# RockBlock_Breakout.net
KiCad netlist of a schematic drawn in EAGLE
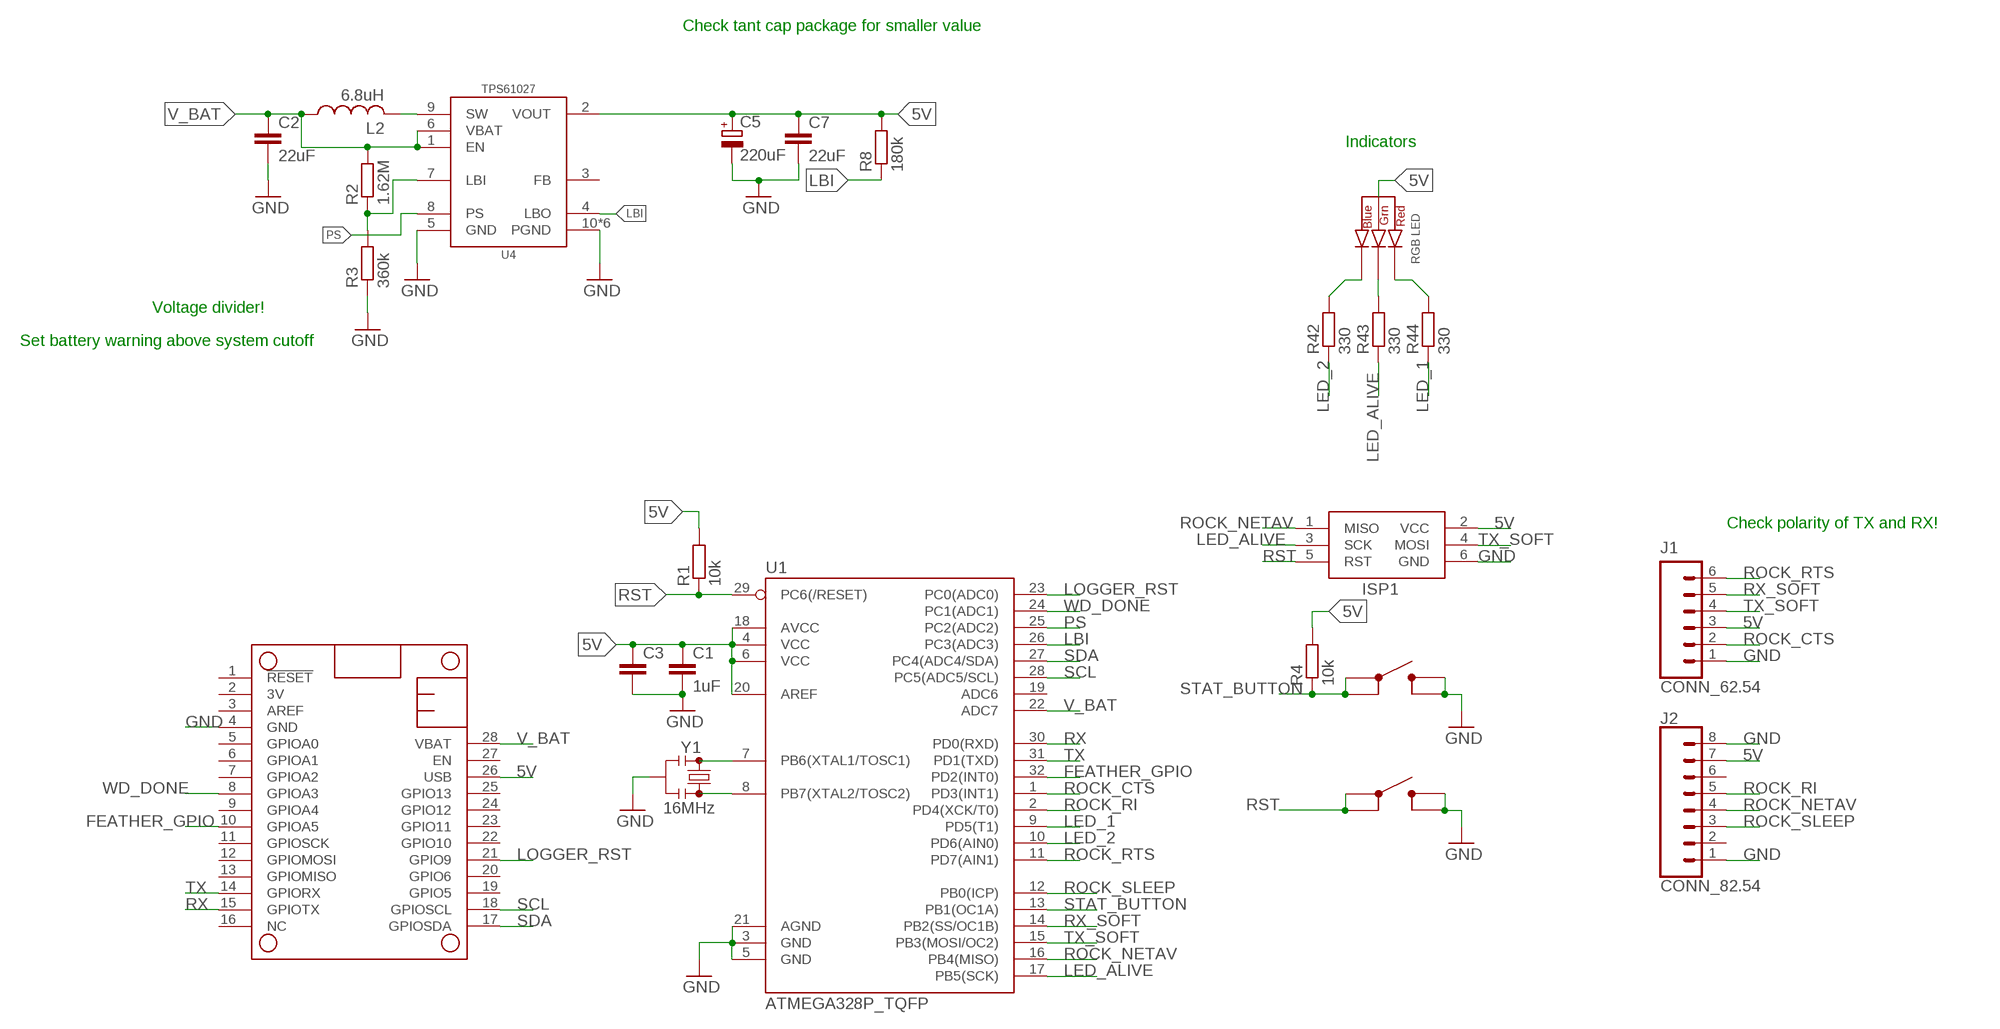
[diagram p0: schematic, sheet 1]

(export (version "E")
  (design (tool "Eeschema 10.0.6"))
  (components
    (comp (ref "C1")
      (value "1uF")
      (footprint "eagle-import:C0603")
      (libsource (lib "eagle-import") (part "C-EUC0603"))
    )
    (comp (ref "C2")
      (value "22uF")
      (footprint "eagle-import:C0805")
      (fields (field (name "MF") "Murata") (field (name "MPN") "GRM219R61C226ME15L"))
      (libsource (lib "eagle-import") (part "C-EUC080522UF"))
    )
    (comp (ref "C3")
      (value "C-EUC0402")
      (footprint "eagle-import:C0402")
      (libsource (lib "eagle-import") (part "C-EUC0402"))
    )
    (comp (ref "C5")
      (value "220uF")
      (footprint "eagle-import:C2917")
      (fields (field (name "MF") "AVX") (field (name "MPN") "TPSY227K010R0100"))
      (libsource (lib "eagle-import") (part "CTANT_EU2917"))
    )
    (comp (ref "C7")
      (value "22uF")
      (footprint "eagle-import:C0805")
      (fields (field (name "MF") "Murata") (field (name "MPN") "GRM219R61C226ME15L"))
      (libsource (lib "eagle-import") (part "C-EUC080522UF"))
    )
    (comp (ref "D5")
      (value "CLVBA-FKA")
      (footprint "eagle-import:CLVBA-FKA")
      (fields (field (name "MF") "Cree") (field (name "MPN") "CLVBA-FKA-CAEDH8BBB7A363"))
      (libsource (lib "eagle-import") (part "CLVBA-FKA"))
    )
    (comp (ref "ISP1")
      (value "AVRISP-6")
      (footprint "eagle-import:AVRISP")
      (libsource (lib "eagle-import") (part "AVRISP-6"))
    )
    (comp (ref "J1")
      (value "CONN_62.54")
      (footprint "eagle-import:1X06")
      (libsource (lib "eagle-import") (part "CONN_62.54"))
    )
    (comp (ref "J2")
      (value "CONN_82.54")
      (footprint "eagle-import:1X08")
      (libsource (lib "eagle-import") (part "CONN_82.54"))
    )
    (comp (ref "L2")
      (value "6.8uH")
      (footprint "eagle-import:WE-TPC(4.8X4.8)")
      (fields (field (name "MF") "Wurth") (field (name "MPN") "744042006"))
      (libsource (lib "eagle-import") (part "INDUCTORTPC_4.8X4.8"))
    )
    (comp (ref "MS1")
      (value "FEATHERWINGLAYOUT")
      (footprint "eagle-import:FEATHERWING_MIN")
      (libsource (lib "eagle-import") (part "FEATHERWINGLAYOUT"))
    )
    (comp (ref "R1")
      (value "10k")
      (footprint "eagle-import:R0402")
      (fields (field (name "MF") "Yageo"))
      (libsource (lib "eagle-import") (part "R-EU_R0402"))
    )
    (comp (ref "R2")
      (value "1.62M")
      (footprint "eagle-import:R0603")
      (fields (field (name "MF") "Stackpole") (field (name "MPN") "RMCF0603FT1M62"))
      (libsource (lib "eagle-import") (part "R-EU_R06031.62M"))
    )
    (comp (ref "R3")
      (value "360k")
      (footprint "eagle-import:R0603")
      (fields (field (name "MF") "Yageo") (field (name "MPN") "RC0603FR-07360KL"))
      (libsource (lib "eagle-import") (part "R-EU_R0603360K"))
    )
    (comp (ref "R4")
      (value "10k")
      (footprint "eagle-import:R0402")
      (fields (field (name "MF") "Yageo"))
      (libsource (lib "eagle-import") (part "R-EU_R0402"))
    )
    (comp (ref "R8")
      (value "180k")
      (footprint "eagle-import:R0603")
      (fields (field (name "MF") "Panasonic") (field (name "MPN") "ERJ-3EKF1803V"))
      (libsource (lib "eagle-import") (part "R-EU_R0603180K"))
    )
    (comp (ref "R42")
      (value "330")
      (footprint "eagle-import:R0402")
      (fields
        (field (name "MF") "Yageo")
        (field (name "MPN") "RC0402FR-07330RL")
        (field (name "MPN_1") "RC0603FR-07330RL")
      )
      (libsource (lib "eagle-import") (part "R-EU_R0402330"))
    )
    (comp (ref "R43")
      (value "330")
      (footprint "eagle-import:R0402")
      (fields
        (field (name "MF") "Yageo")
        (field (name "MPN") "RC0402FR-07330RL")
        (field (name "MPN_1") "RC0603FR-07330RL")
      )
      (libsource (lib "eagle-import") (part "R-EU_R0402330"))
    )
    (comp (ref "R44")
      (value "330")
      (footprint "eagle-import:R0402")
      (fields
        (field (name "MF") "Yageo")
        (field (name "MPN") "RC0402FR-07330RL")
        (field (name "MPN_1") "RC0603FR-07330RL")
      )
      (libsource (lib "eagle-import") (part "R-EU_R0402330"))
    )
    (comp (ref "S1")
      (value "BUTTON4.2X3.2")
      (footprint "eagle-import:SWITCH_4.2X3.2")
      (fields (field (name "MF") "C&K") (field (name "MPN") "PTS810 SJG 250 SMTR LFS"))
      (libsource (lib "eagle-import") (part "BUTTON4.2X3.2"))
    )
    (comp (ref "S2")
      (value "BUTTON4.2X3.2")
      (footprint "eagle-import:SWITCH_4.2X3.2")
      (fields (field (name "MF") "C&K") (field (name "MPN") "PTS810 SJG 250 SMTR LFS"))
      (libsource (lib "eagle-import") (part "BUTTON4.2X3.2"))
    )
    (comp (ref "U1")
      (value "ATMEGA328P_TQFP")
      (footprint "eagle-import:TQFP32-08")
      (fields (field (name "MF") "Atmel") (field (name "MPN") "ATMEGA328PB-AUR"))
      (libsource (lib "eagle-import") (part "ATMEGA328P_TQFP"))
    )
    (comp (ref "U4")
      (value "TPS61027DRC")
      (footprint "eagle-import:DRC0010J")
      (fields (field (name "DISP") "TPS61027") (field (name "MF") "TI") (field (name "MPN") "TPS61027DRCR"))
      (libsource (lib "eagle-import") (part "TPS6102DRC7"))
    )
    (comp (ref "Y1")
      (value "16MHz")
      (footprint "eagle-import:RESONATOR-SMD-3.2X1.3")
      (fields (field (name "MF") "Murata") (field (name "MPN") "CSTNE16M0V530000R0"))
      (libsource (lib "eagle-import") (part "RESONATORSMD_3.2X1.316MHZ"))
    )
  )
  (nets
    (net (code "1") (name "/3V") (class "Default")
      (node (ref "MS1") (pin "2") (pinfunction "3V_2") (pintype "power_in"))
    )
    (net (code "2") (name "/FEATHER_GPIO") (class "Default")
      (node (ref "MS1") (pin "10") (pinfunction "GPIOA5_10") (pintype "bidirectional"))
      (node (ref "U1") (pin "32") (pinfunction "PD2(INT0)_32") (pintype "bidirectional"))
    )
    (net (code "3") (name "/LED_1") (class "Default")
      (node (ref "R44") (pin "1") (pinfunction "1_1") (pintype "passive"))
      (node (ref "U1") (pin "9") (pinfunction "PD5(T1)_9") (pintype "bidirectional"))
    )
    (net (code "4") (name "/LED_2") (class "Default")
      (node (ref "R42") (pin "1") (pinfunction "1_1") (pintype "passive"))
      (node (ref "U1") (pin "10") (pinfunction "PD6(AIN0)_10") (pintype "bidirectional"))
    )
    (net (code "5") (name "/LED_ALIVE") (class "Default")
      (node (ref "ISP1") (pin "3") (pinfunction "SCK_3") (pintype "output"))
      (node (ref "R43") (pin "1") (pinfunction "1_1") (pintype "passive"))
      (node (ref "U1") (pin "17") (pinfunction "PB5(SCK)_17") (pintype "bidirectional"))
    )
    (net (code "6") (name "/LOGGER_RST") (class "Default")
      (node (ref "MS1") (pin "21") (pinfunction "GPIO9_21") (pintype "bidirectional"))
      (node (ref "U1") (pin "23") (pinfunction "PC0(ADC0)_23") (pintype "bidirectional"))
    )
    (net (code "7") (name "/ROCK_CTS") (class "Default")
      (node (ref "J1") (pin "2") (pinfunction "2_2") (pintype "passive"))
      (node (ref "U1") (pin "1") (pinfunction "PD3(INT1)_1") (pintype "bidirectional"))
    )
    (net (code "8") (name "/ROCK_NETAV") (class "Default")
      (node (ref "ISP1") (pin "1") (pinfunction "MISO_1") (pintype "input"))
      (node (ref "J2") (pin "4") (pinfunction "4_4") (pintype "passive"))
      (node (ref "U1") (pin "16") (pinfunction "PB4(MISO)_16") (pintype "bidirectional"))
    )
    (net (code "9") (name "/ROCK_RI") (class "Default")
      (node (ref "J2") (pin "5") (pinfunction "5_5") (pintype "passive"))
      (node (ref "U1") (pin "2") (pinfunction "PD4(XCK/T0)_2") (pintype "bidirectional"))
    )
    (net (code "10") (name "/ROCK_RTS") (class "Default")
      (node (ref "J1") (pin "6") (pinfunction "6_6") (pintype "passive"))
      (node (ref "U1") (pin "11") (pinfunction "PD7(AIN1)_11") (pintype "bidirectional"))
    )
    (net (code "11") (name "/ROCK_SLEEP") (class "Default")
      (node (ref "J2") (pin "3") (pinfunction "3_3") (pintype "passive"))
      (node (ref "U1") (pin "12") (pinfunction "PB0(ICP)_12") (pintype "bidirectional"))
    )
    (net (code "12") (name "/RX") (class "Default")
      (node (ref "MS1") (pin "15") (pinfunction "GPIOTX_15") (pintype "bidirectional"))
      (node (ref "U1") (pin "30") (pinfunction "PD0(RXD)_30") (pintype "bidirectional"))
    )
    (net (code "13") (name "/RX_SOFT") (class "Default")
      (node (ref "J1") (pin "5") (pinfunction "5_5") (pintype "passive"))
      (node (ref "U1") (pin "14") (pinfunction "PB2(SS/OC1B)_14") (pintype "bidirectional"))
    )
    (net (code "14") (name "/SCL") (class "Default")
      (node (ref "MS1") (pin "18") (pinfunction "GPIOSCL_18") (pintype "bidirectional"))
      (node (ref "U1") (pin "28") (pinfunction "PC5(ADC5/SCL)_28") (pintype "bidirectional"))
    )
    (net (code "15") (name "/SDA") (class "Default")
      (node (ref "MS1") (pin "17") (pinfunction "GPIOSDA_17") (pintype "bidirectional"))
      (node (ref "U1") (pin "27") (pinfunction "PC4(ADC4/SDA)_27") (pintype "bidirectional"))
    )
    (net (code "16") (name "/STAT_BUTTON") (class "Default")
      (node (ref "R4") (pin "1") (pinfunction "1_1") (pintype "passive"))
      (node (ref "S1") (pin "1") (pinfunction "1_1") (pintype "bidirectional"))
      (node (ref "S1") (pin "2") (pinfunction "2_2") (pintype "bidirectional"))
      (node (ref "U1") (pin "13") (pinfunction "PB1(OC1A)_13") (pintype "bidirectional"))
    )
    (net (code "17") (name "/TX") (class "Default")
      (node (ref "MS1") (pin "14") (pinfunction "GPIORX_14") (pintype "bidirectional"))
      (node (ref "U1") (pin "31") (pinfunction "PD1(TXD)_31") (pintype "bidirectional"))
    )
    (net (code "18") (name "/TX_SOFT") (class "Default")
      (node (ref "ISP1") (pin "4") (pinfunction "MOSI_4") (pintype "output"))
      (node (ref "J1") (pin "4") (pinfunction "4_4") (pintype "passive"))
      (node (ref "U1") (pin "15") (pinfunction "PB3(MOSI/OC2)_15") (pintype "bidirectional"))
    )
    (net (code "19") (name "/WD_DONE") (class "Default")
      (node (ref "MS1") (pin "8") (pinfunction "GPIOA3_8") (pintype "bidirectional"))
      (node (ref "U1") (pin "24") (pinfunction "PC1(ADC1)_24") (pintype "bidirectional"))
    )
    (net (code "20") (name "5V") (class "Default")
      (node (ref "C1") (pin "1") (pinfunction "1_1") (pintype "passive"))
      (node (ref "C3") (pin "1") (pinfunction "1_1") (pintype "passive"))
      (node (ref "C5") (pin "+") (pinfunction "+_+") (pintype "passive"))
      (node (ref "C7") (pin "1") (pinfunction "1_1") (pintype "passive"))
      (node (ref "D5") (pin "2") (pinfunction "ANODE_2") (pintype "bidirectional"))
      (node (ref "ISP1") (pin "2") (pinfunction "VCC_2") (pintype "power_in"))
      (node (ref "J1") (pin "3") (pinfunction "3_3") (pintype "passive"))
      (node (ref "J2") (pin "7") (pinfunction "7_7") (pintype "passive"))
      (node (ref "MS1") (pin "26") (pinfunction "USB_26") (pintype "power_in"))
      (node (ref "R1") (pin "2") (pinfunction "2_2") (pintype "passive"))
      (node (ref "R4") (pin "2") (pinfunction "2_2") (pintype "passive"))
      (node (ref "R8") (pin "2") (pinfunction "2_2") (pintype "passive"))
      (node (ref "U1") (pin "18") (pinfunction "AVCC_18") (pintype "bidirectional"))
      (node (ref "U1") (pin "20") (pinfunction "AREF_20") (pintype "bidirectional"))
      (node (ref "U1") (pin "4") (pinfunction "VCC_4") (pintype "bidirectional"))
      (node (ref "U1") (pin "6") (pinfunction "VCC_6") (pintype "bidirectional"))
      (node (ref "U4") (pin "2") (pinfunction "VOUT_2") (pintype "power_in"))
    )
    (net (code "21") (name "GND") (class "Default")
      (node (ref "C1") (pin "2") (pinfunction "2_2") (pintype "passive"))
      (node (ref "C2") (pin "2") (pinfunction "2_2") (pintype "passive"))
      (node (ref "C3") (pin "2") (pinfunction "2_2") (pintype "passive"))
      (node (ref "C5") (pin "-") (pinfunction "-_-") (pintype "passive"))
      (node (ref "C7") (pin "2") (pinfunction "2_2") (pintype "passive"))
      (node (ref "ISP1") (pin "6") (pinfunction "GND_6") (pintype "power_in"))
      (node (ref "J1") (pin "1") (pinfunction "1_1") (pintype "passive"))
      (node (ref "J2") (pin "1") (pinfunction "1_1") (pintype "passive"))
      (node (ref "J2") (pin "8") (pinfunction "8_8") (pintype "passive"))
      (node (ref "MS1") (pin "4") (pinfunction "GND_4") (pintype "power_in"))
      (node (ref "R3") (pin "1") (pinfunction "1_1") (pintype "passive"))
      (node (ref "S1") (pin "3") (pinfunction "4_3") (pintype "bidirectional"))
      (node (ref "S1") (pin "4") (pinfunction "3_4") (pintype "bidirectional"))
      (node (ref "S2") (pin "3") (pinfunction "4_3") (pintype "bidirectional"))
      (node (ref "S2") (pin "4") (pinfunction "3_4") (pintype "bidirectional"))
      (node (ref "U1") (pin "21") (pinfunction "AGND_21") (pintype "bidirectional"))
      (node (ref "U1") (pin "3") (pinfunction "GND_3") (pintype "bidirectional"))
      (node (ref "U1") (pin "5") (pinfunction "GND_5") (pintype "bidirectional"))
      (node (ref "U4") (pin "10") (pinfunction "PGND_10") (pintype "power_in"))
      (node (ref "U4") (pin "5") (pinfunction "GND_5") (pintype "power_in"))
      (node (ref "U4") (pin "EP@1") (pinfunction "PGND_EP@1") (pintype "power_in"))
      (node (ref "U4") (pin "EP@2") (pinfunction "PGND_EP@2") (pintype "power_in"))
      (node (ref "U4") (pin "EP@3") (pinfunction "PGND_EP@3") (pintype "power_in"))
      (node (ref "U4") (pin "EP@4") (pinfunction "PGND_EP@4") (pintype "power_in"))
      (node (ref "U4") (pin "EP@5") (pinfunction "PGND_EP@5") (pintype "power_in"))
      (node (ref "Y1") (pin "2") (pinfunction "2_2") (pintype "passive"))
    )
    (net (code "22") (name "LBI") (class "Default")
      (node (ref "R8") (pin "1") (pinfunction "1_1") (pintype "passive"))
      (node (ref "U1") (pin "26") (pinfunction "PC3(ADC3)_26") (pintype "bidirectional"))
      (node (ref "U4") (pin "4") (pinfunction "LBO_4") (pintype "output"))
    )
    (net (code "23") (name "Net-(D5-BLUE_CATH)") (class "Default")
      (node (ref "D5") (pin "3") (pinfunction "BLUE_CATH_3") (pintype "bidirectional"))
      (node (ref "R42") (pin "2") (pinfunction "2_2") (pintype "passive"))
    )
    (net (code "24") (name "Net-(D5-GREEN_CATH)") (class "Default")
      (node (ref "D5") (pin "4") (pinfunction "GREEN_CATH_4") (pintype "bidirectional"))
      (node (ref "R43") (pin "2") (pinfunction "2_2") (pintype "passive"))
    )
    (net (code "25") (name "Net-(D5-RED_CATH)") (class "Default")
      (node (ref "D5") (pin "1") (pinfunction "RED_CATH_1") (pintype "bidirectional"))
      (node (ref "R44") (pin "2") (pinfunction "2_2") (pintype "passive"))
    )
    (net (code "26") (name "Net-(U1-PB6(XTAL1{slash}TOSC1))") (class "Default")
      (node (ref "U1") (pin "7") (pinfunction "PB6(XTAL1/TOSC1)_7") (pintype "bidirectional"))
      (node (ref "Y1") (pin "1") (pinfunction "1_1") (pintype "passive"))
    )
    (net (code "27") (name "Net-(U1-PB7(XTAL2{slash}TOSC2))") (class "Default")
      (node (ref "U1") (pin "8") (pinfunction "PB7(XTAL2/TOSC2)_8") (pintype "bidirectional"))
      (node (ref "Y1") (pin "3") (pinfunction "3_3") (pintype "passive"))
    )
    (net (code "28") (name "Net-(U4-LBI)") (class "Default")
      (node (ref "R2") (pin "1") (pinfunction "1_1") (pintype "passive"))
      (node (ref "R3") (pin "2") (pinfunction "2_2") (pintype "passive"))
      (node (ref "U4") (pin "7") (pinfunction "LBI_7") (pintype "input"))
    )
    (net (code "29") (name "Net-(U4-SW)") (class "Default")
      (node (ref "L2") (pin "2") (pinfunction "2_2") (pintype "passive"))
      (node (ref "U4") (pin "9") (pinfunction "SW_9") (pintype "power_in"))
    )
    (net (code "30") (name "PS") (class "Default")
      (node (ref "U1") (pin "25") (pinfunction "PC2(ADC2)_25") (pintype "bidirectional"))
      (node (ref "U4") (pin "8") (pinfunction "PS_8") (pintype "input"))
    )
    (net (code "31") (name "RST") (class "Default")
      (node (ref "ISP1") (pin "5") (pinfunction "RST_5") (pintype "output"))
      (node (ref "R1") (pin "1") (pinfunction "1_1") (pintype "passive"))
      (node (ref "S2") (pin "1") (pinfunction "1_1") (pintype "bidirectional"))
      (node (ref "S2") (pin "2") (pinfunction "2_2") (pintype "bidirectional"))
      (node (ref "U1") (pin "29") (pinfunction "PC6(/RESET)_29") (pintype "bidirectional"))
    )
    (net (code "32") (name "V_BAT") (class "Default")
      (node (ref "C2") (pin "1") (pinfunction "1_1") (pintype "passive"))
      (node (ref "L2") (pin "1") (pinfunction "1_1") (pintype "passive"))
      (node (ref "MS1") (pin "28") (pinfunction "VBAT_28") (pintype "power_in"))
      (node (ref "R2") (pin "2") (pinfunction "2_2") (pintype "passive"))
      (node (ref "U1") (pin "22") (pinfunction "ADC7_22") (pintype "bidirectional"))
      (node (ref "U4") (pin "1") (pinfunction "EN_1") (pintype "input"))
      (node (ref "U4") (pin "6") (pinfunction "VBAT_6") (pintype "power_in"))
    )
    (net (code "33") (name "unconnected-(J2-Pad2)") (class "Default")
      (node (ref "J2") (pin "2") (pinfunction "2_2") (pintype "passive"))
    )
    (net (code "34") (name "unconnected-(J2-Pad6)") (class "Default")
      (node (ref "J2") (pin "6") (pinfunction "6_6") (pintype "passive"))
    )
    (net (code "35") (name "unconnected-(MS1-AREF-Pad3)") (class "Default")
      (node (ref "MS1") (pin "3") (pinfunction "AREF_3") (pintype "passive"))
    )
    (net (code "36") (name "unconnected-(MS1-EN-Pad27)") (class "Default")
      (node (ref "MS1") (pin "27") (pinfunction "EN_27") (pintype "passive"))
    )
    (net (code "37") (name "unconnected-(MS1-GPIO5-Pad19)") (class "Default")
      (node (ref "MS1") (pin "19") (pinfunction "GPIO5_19") (pintype "bidirectional"))
    )
    (net (code "38") (name "unconnected-(MS1-GPIO6-Pad20)") (class "Default")
      (node (ref "MS1") (pin "20") (pinfunction "GPIO6_20") (pintype "bidirectional"))
    )
    (net (code "39") (name "unconnected-(MS1-GPIO10-Pad22)") (class "Default")
      (node (ref "MS1") (pin "22") (pinfunction "GPIO10_22") (pintype "bidirectional"))
    )
    (net (code "40") (name "unconnected-(MS1-GPIO11-Pad23)") (class "Default")
      (node (ref "MS1") (pin "23") (pinfunction "GPIO11_23") (pintype "bidirectional"))
    )
    (net (code "41") (name "unconnected-(MS1-GPIO12-Pad24)") (class "Default")
      (node (ref "MS1") (pin "24") (pinfunction "GPIO12_24") (pintype "bidirectional"))
    )
    (net (code "42") (name "unconnected-(MS1-GPIO13-Pad25)") (class "Default")
      (node (ref "MS1") (pin "25") (pinfunction "GPIO13_25") (pintype "bidirectional"))
    )
    (net (code "43") (name "unconnected-(MS1-GPIOA0-Pad5)") (class "Default")
      (node (ref "MS1") (pin "5") (pinfunction "GPIOA0_5") (pintype "bidirectional"))
    )
    (net (code "44") (name "unconnected-(MS1-GPIOA1-Pad6)") (class "Default")
      (node (ref "MS1") (pin "6") (pinfunction "GPIOA1_6") (pintype "bidirectional"))
    )
    (net (code "45") (name "unconnected-(MS1-GPIOA2-Pad7)") (class "Default")
      (node (ref "MS1") (pin "7") (pinfunction "GPIOA2_7") (pintype "bidirectional"))
    )
    (net (code "46") (name "unconnected-(MS1-GPIOA4-Pad9)") (class "Default")
      (node (ref "MS1") (pin "9") (pinfunction "GPIOA4_9") (pintype "bidirectional"))
    )
    (net (code "47") (name "unconnected-(MS1-GPIOMISO-Pad13)") (class "Default")
      (node (ref "MS1") (pin "13") (pinfunction "GPIOMISO_13") (pintype "bidirectional"))
    )
    (net (code "48") (name "unconnected-(MS1-GPIOMOSI-Pad12)") (class "Default")
      (node (ref "MS1") (pin "12") (pinfunction "GPIOMOSI_12") (pintype "bidirectional"))
    )
    (net (code "49") (name "unconnected-(MS1-GPIOSCK-Pad11)") (class "Default")
      (node (ref "MS1") (pin "11") (pinfunction "GPIOSCK_11") (pintype "bidirectional"))
    )
    (net (code "50") (name "unconnected-(MS1-NC-Pad16)") (class "Default")
      (node (ref "MS1") (pin "16") (pinfunction "NC_16") (pintype "passive"))
    )
    (net (code "51") (name "unconnected-(MS1-~{RESET}-Pad1)") (class "Default")
      (node (ref "MS1") (pin "1") (pinfunction "~{RESET}_1") (pintype "input"))
    )
    (net (code "52") (name "unconnected-(U1-ADC6-Pad19)") (class "Default")
      (node (ref "U1") (pin "19") (pinfunction "ADC6_19") (pintype "bidirectional"))
    )
    (net (code "53") (name "unconnected-(U4-FB-Pad3)") (class "Default")
      (node (ref "U4") (pin "3") (pinfunction "FB_3") (pintype "input"))
    )
  )
)
